# Controller.net
KiCad netlist of a schematic drawn in Altium Designer
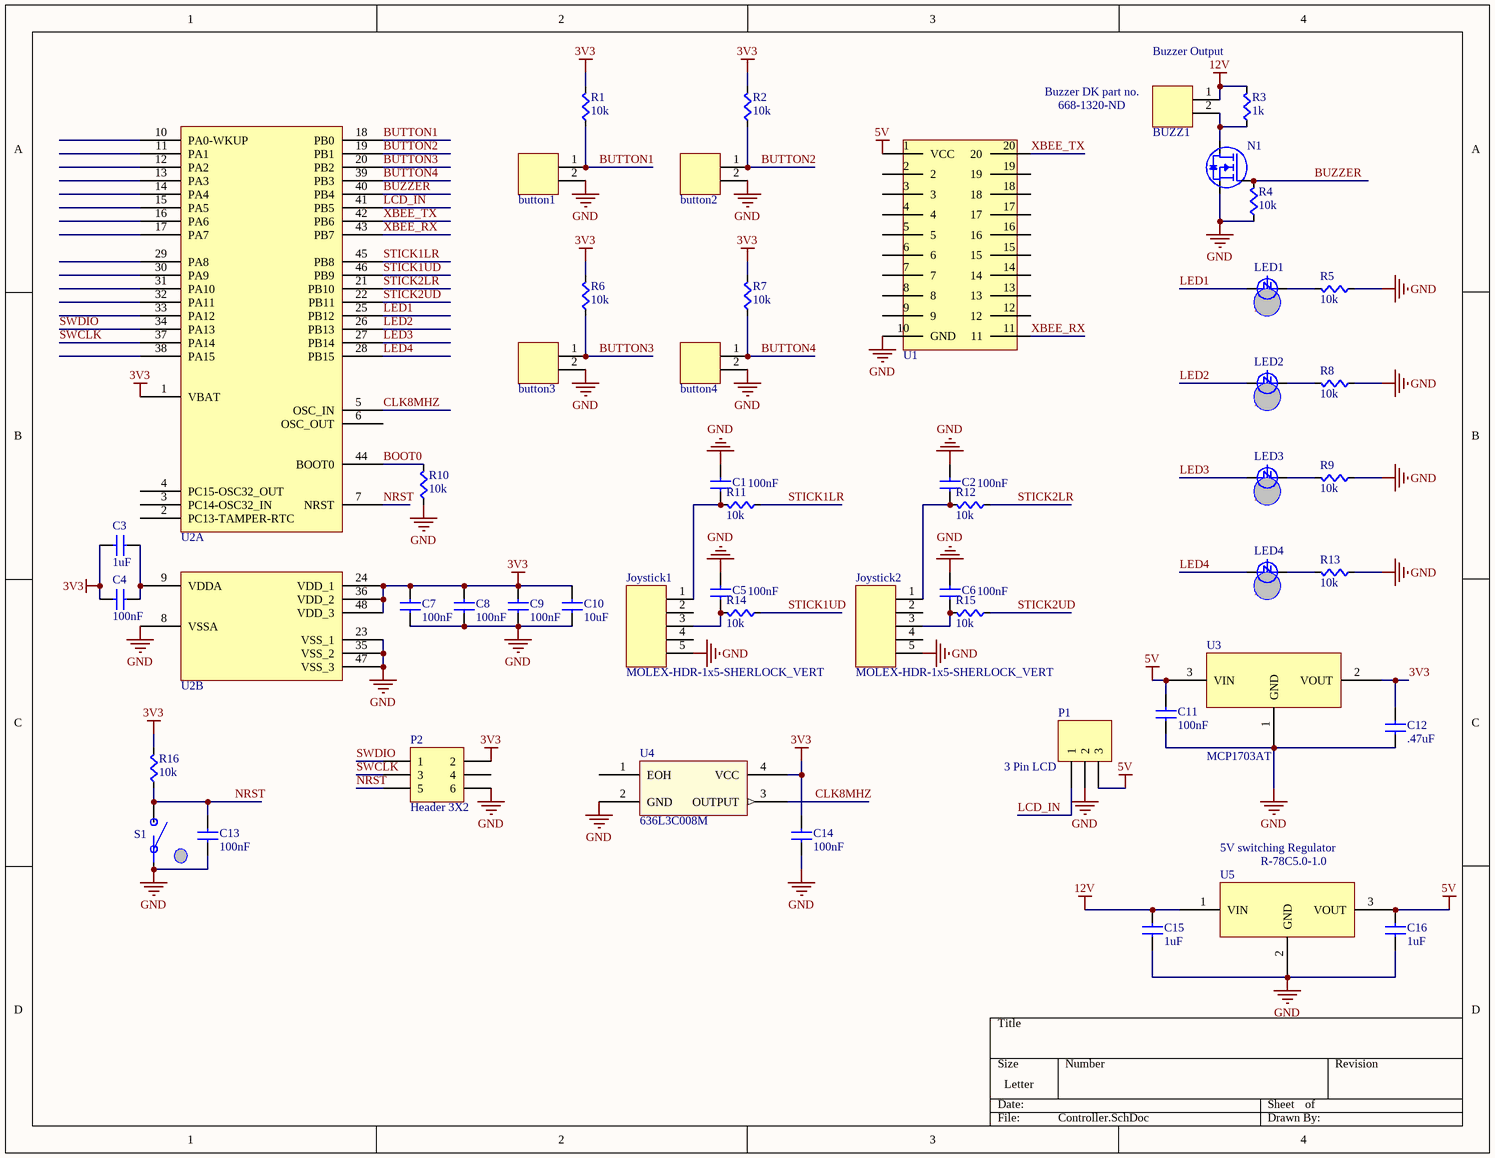
[diagram p0: Controller.SchDoc]

(export (version "E")
  (design (tool "Eeschema 10.0.6"))
  (components
    (comp (ref "button1")
      (value "2-pin Horz Sherlock")
      (footprint "MOLEX-HDR-1X2-SHERLOCK-HORZ")
      (fields
        (field (name "MANUFACTURER PART NUMBER") "0353630260")
        (field (name "MANUFACTURER") "Molex Inc")
      )
      (libsource (lib "SubjuGator8") (part "MOLEX-HDR-1x2-SHERLOCK_RA"))
    )
    (comp (ref "button2")
      (value "2-pin Horz Sherlock")
      (footprint "MOLEX-HDR-1X2-SHERLOCK-HORZ")
      (fields
        (field (name "MANUFACTURER PART NUMBER") "0353630260")
        (field (name "MANUFACTURER") "Molex Inc")
      )
      (libsource (lib "SubjuGator8") (part "MOLEX-HDR-1x2-SHERLOCK_RA"))
    )
    (comp (ref "button3")
      (value "2-pin Horz Sherlock")
      (footprint "MOLEX-HDR-1X2-SHERLOCK-HORZ")
      (fields
        (field (name "MANUFACTURER PART NUMBER") "0353630260")
        (field (name "MANUFACTURER") "Molex Inc")
      )
      (libsource (lib "SubjuGator8") (part "MOLEX-HDR-1x2-SHERLOCK_RA"))
    )
    (comp (ref "button4")
      (value "2-pin Horz Sherlock")
      (footprint "MOLEX-HDR-1X2-SHERLOCK-HORZ")
      (fields
        (field (name "MANUFACTURER PART NUMBER") "0353630260")
        (field (name "MANUFACTURER") "Molex Inc")
      )
      (libsource (lib "SubjuGator8") (part "MOLEX-HDR-1x2-SHERLOCK_RA"))
    )
    (comp (ref "BUZZ1")
      (value "2-pin Horz Sherlock")
      (footprint "MOLEX-HDR-1X2-SHERLOCK-HORZ")
      (fields
        (field (name "MANUFACTURER PART NUMBER") "0353630260")
        (field (name "MANUFACTURER") "Molex Inc")
      )
      (libsource (lib "SubjuGator8") (part "MOLEX-HDR-1x2-SHERLOCK_RA"))
    )
    (comp (ref "C1")
      (value "100nF")
      (footprint "CAPC0603")
      (fields (field (name "Comment") "Cap"))
      (libsource (lib "SubjuGator8") (part "Cap"))
    )
    (comp (ref "C2")
      (value "100nF")
      (footprint "CAPC0603")
      (fields (field (name "Comment") "Cap"))
      (libsource (lib "SubjuGator8") (part "Cap"))
    )
    (comp (ref "C3")
      (value "1uF")
      (footprint "CAPC0603")
      (fields (field (name "Comment") "Cap"))
      (libsource (lib "SubjuGator8") (part "Cap"))
    )
    (comp (ref "C4")
      (value "100nF")
      (footprint "CAPC0603")
      (fields (field (name "Comment") "Cap"))
      (libsource (lib "SubjuGator8") (part "Cap"))
    )
    (comp (ref "C5")
      (value "100nF")
      (footprint "CAPC0603")
      (fields (field (name "Comment") "Cap"))
      (libsource (lib "SubjuGator8") (part "Cap"))
    )
    (comp (ref "C6")
      (value "100nF")
      (footprint "CAPC0603")
      (fields (field (name "Comment") "Cap"))
      (libsource (lib "SubjuGator8") (part "Cap"))
    )
    (comp (ref "C7")
      (value "100nF")
      (footprint "CAPC0603")
      (fields (field (name "Comment") "Cap"))
      (libsource (lib "SubjuGator8") (part "Cap"))
    )
    (comp (ref "C8")
      (value "100nF")
      (footprint "CAPC0603")
      (fields (field (name "Comment") "Cap"))
      (libsource (lib "SubjuGator8") (part "Cap"))
    )
    (comp (ref "C9")
      (value "100nF")
      (footprint "CAPC0603")
      (fields (field (name "Comment") "Cap"))
      (libsource (lib "SubjuGator8") (part "Cap"))
    )
    (comp (ref "C10")
      (value "10uF")
      (footprint "CAPC1206")
      (fields (field (name "Comment") "Cap"))
      (libsource (lib "SubjuGator8") (part "Cap"))
    )
    (comp (ref "C11")
      (value "100nF")
      (footprint "CAPC1206")
      (fields (field (name "Comment") "Cap"))
      (libsource (lib "SubjuGator8") (part "Cap"))
    )
    (comp (ref "C12")
      (value ".47uF")
      (footprint "CAPC1206")
      (fields (field (name "Comment") "Cap"))
      (libsource (lib "SubjuGator8") (part "Cap"))
    )
    (comp (ref "C13")
      (value "100nF")
      (footprint "CAPC0603")
      (fields (field (name "Comment") "Cap"))
      (libsource (lib "SubjuGator8") (part "Cap"))
    )
    (comp (ref "C14")
      (value "100nF")
      (footprint "CAPC0603")
      (fields (field (name "Comment") "Cap"))
      (libsource (lib "SubjuGator8") (part "Cap"))
    )
    (comp (ref "C15")
      (value "1uF")
      (footprint "CAPC1206")
      (fields (field (name "Comment") "Cap"))
      (libsource (lib "SubjuGator8") (part "Cap"))
    )
    (comp (ref "C16")
      (value "1uF")
      (footprint "CAPC1206")
      (fields (field (name "Comment") "Cap"))
      (libsource (lib "SubjuGator8") (part "Cap"))
    )
    (comp (ref "Joystick1")
      (value "MOLEX-HDR-1x5-SHERLOCK_VERT")
      (footprint "MOLEX-HDR-1X5-SHERLOCK-VERT")
      (libsource (lib "SubjuGator8") (part "MOLEX-HDR-1x5-SHERLOCK_VERT"))
    )
    (comp (ref "Joystick2")
      (value "MOLEX-HDR-1x5-SHERLOCK_VERT")
      (footprint "MOLEX-HDR-1X5-SHERLOCK-VERT")
      (libsource (lib "SubjuGator8") (part "MOLEX-HDR-1x5-SHERLOCK_VERT"))
    )
    (comp (ref "LED1")
      (value "LED")
      (footprint "LED0603")
      (fields (field (name "COLOR") "Red"))
      (libsource (lib "SubjuGator8") (part "LED"))
    )
    (comp (ref "LED2")
      (value "LED")
      (footprint "LED0603")
      (fields (field (name "COLOR") "Red"))
      (libsource (lib "SubjuGator8") (part "LED"))
    )
    (comp (ref "LED3")
      (value "LED")
      (footprint "LED0603")
      (fields (field (name "COLOR") "Red"))
      (libsource (lib "SubjuGator8") (part "LED"))
    )
    (comp (ref "LED4")
      (value "LED")
      (footprint "LED0603")
      (fields (field (name "COLOR") "Red"))
      (libsource (lib "SubjuGator8") (part "LED"))
    )
    (comp (ref "N1")
      (value "NMOSFET")
      (footprint "2N7002P,215")
      (description "NMOSFET Template")
      (libsource (lib "SubjuGator8") (part "NMOSFET"))
    )
    (comp (ref "P1")
      (value "3 Pin LCD")
      (footprint "HDR1X3")
      (description "NHD-0420D3Z-NSW-BBW-V3-ND")
      (fields (field (name "PUBLISHER") "Altium Limited"))
      (libsource (lib "Miscellaneous Connectors") (part "Header 3"))
    )
    (comp (ref "P2")
      (value "Header 3X2")
      (footprint "HDR2X3")
      (description "Header, 3-Pin, Dual row")
      (fields (field (name "PUBLISHER") "Altium Limited"))
      (libsource (lib "Miscellaneous Connectors") (part "Header 3X2"))
    )
    (comp (ref "R1")
      (value "10k")
      (footprint "RES0603")
      (fields (field (name "Comment") "Res"))
      (libsource (lib "SubjuGator8") (part "Res"))
    )
    (comp (ref "R2")
      (value "10k")
      (footprint "RES0603")
      (fields (field (name "Comment") "Res"))
      (libsource (lib "SubjuGator8") (part "Res"))
    )
    (comp (ref "R3")
      (value "1k")
      (footprint "RES0603")
      (fields (field (name "Comment") "Res"))
      (libsource (lib "SubjuGator8") (part "Res"))
    )
    (comp (ref "R4")
      (value "10k")
      (footprint "RES0603")
      (fields (field (name "Comment") "Res"))
      (libsource (lib "SubjuGator8") (part "Res"))
    )
    (comp (ref "R5")
      (value "10k")
      (footprint "RES0603")
      (fields (field (name "Comment") "Res"))
      (libsource (lib "SubjuGator8") (part "Res"))
    )
    (comp (ref "R6")
      (value "10k")
      (footprint "RES0603")
      (fields (field (name "Comment") "Res"))
      (libsource (lib "SubjuGator8") (part "Res"))
    )
    (comp (ref "R7")
      (value "10k")
      (footprint "RES0603")
      (fields (field (name "Comment") "Res"))
      (libsource (lib "SubjuGator8") (part "Res"))
    )
    (comp (ref "R8")
      (value "10k")
      (footprint "RES0603")
      (fields (field (name "Comment") "Res"))
      (libsource (lib "SubjuGator8") (part "Res"))
    )
    (comp (ref "R9")
      (value "10k")
      (footprint "RES0603")
      (fields (field (name "Comment") "Res"))
      (libsource (lib "SubjuGator8") (part "Res"))
    )
    (comp (ref "R10")
      (value "10k")
      (footprint "RES0603")
      (fields (field (name "Comment") "Res"))
      (libsource (lib "SubjuGator8") (part "Res"))
    )
    (comp (ref "R11")
      (value "10k")
      (footprint "RES0603")
      (fields (field (name "Comment") "Res"))
      (libsource (lib "SubjuGator8") (part "Res"))
    )
    (comp (ref "R12")
      (value "10k")
      (footprint "RES0603")
      (fields (field (name "Comment") "Res"))
      (libsource (lib "SubjuGator8") (part "Res"))
    )
    (comp (ref "R13")
      (value "10k")
      (footprint "RES0603")
      (fields (field (name "Comment") "Res"))
      (libsource (lib "SubjuGator8") (part "Res"))
    )
    (comp (ref "R14")
      (value "10k")
      (footprint "RES0603")
      (fields (field (name "Comment") "Res"))
      (libsource (lib "SubjuGator8") (part "Res"))
    )
    (comp (ref "R15")
      (value "10k")
      (footprint "RES0603")
      (fields (field (name "Comment") "Res"))
      (libsource (lib "SubjuGator8") (part "Res"))
    )
    (comp (ref "R16")
      (value "10k")
      (footprint "RES0603")
      (fields (field (name "Comment") "Res"))
      (libsource (lib "SubjuGator8") (part "Res"))
    )
    (comp (ref "S1")
      (value "Button")
      (footprint "PTS645xxxxSMTR92")
      (description "SPST Button")
      (libsource (lib "SubjuGator8") (part "Button"))
    )
    (comp (ref "U1")
      (value "XBee")
      (footprint "XBee")
      (description "XBee radio")
      (libsource (lib "SubjuGator8") (part "XBee"))
    )
    (comp (ref "U2")
      (value "STM32F103C8T7")
      (footprint "STM32F103C8T7")
      (description "MCU ARM 32BIT 64K FLASH 48-LQFP")
      (libsource (lib "SubjuGator8") (part "STM32F103C8T7"))
    )
    (comp (ref "U3")
      (value "MCP1703AT")
      (footprint "MCP1703AT-xx02EDB")
      (description "250 mA, 16V, Low Quiescent Current LDO Regulator")
      (libsource (lib "SubjuGator8") (part "MCP1703AT"))
    )
    (comp (ref "U4")
      (value "636L3C008M")
      (footprint "636L3C")
      (description "HCMOS/TTL Clock Oscillator")
      (libsource (lib "SubjuGator8") (part "636L3C"))
    )
    (comp (ref "U5")
      (value "R-78C5.0-1.0")
      (footprint "R-78C5.0-1.0")
      (description "CONV DC/DC 1A 5V OUT SIP VERT")
      (libsource (lib "SubjuGator8") (part "R-78C5.0-1.0"))
    )
  )
  (nets
    (net (code "1") (name "/BOOT0") (class "Default")
      (node (ref "R10") (pin "1") (pinfunction "A_1") (pintype "passive"))
      (node (ref "U2") (pin "44") (pinfunction "BOOT0_44") (pintype "passive"))
    )
    (net (code "2") (name "/BUTTON1") (class "Default")
      (node (ref "R1") (pin "2") (pinfunction "B_2") (pintype "passive"))
      (node (ref "U2") (pin "18") (pinfunction "PB0_18") (pintype "passive"))
      (node (ref "button1") (pin "1") (pinfunction "1_1") (pintype "passive"))
    )
    (net (code "3") (name "/BUTTON2") (class "Default")
      (node (ref "R2") (pin "2") (pinfunction "B_2") (pintype "passive"))
      (node (ref "U2") (pin "19") (pinfunction "PB1_19") (pintype "passive"))
      (node (ref "button2") (pin "1") (pinfunction "1_1") (pintype "passive"))
    )
    (net (code "4") (name "/BUTTON3") (class "Default")
      (node (ref "R6") (pin "2") (pinfunction "B_2") (pintype "passive"))
      (node (ref "U2") (pin "20") (pinfunction "PB2_20") (pintype "passive"))
      (node (ref "button3") (pin "1") (pinfunction "1_1") (pintype "passive"))
    )
    (net (code "5") (name "/BUTTON4") (class "Default")
      (node (ref "R7") (pin "2") (pinfunction "B_2") (pintype "passive"))
      (node (ref "U2") (pin "39") (pinfunction "PB3_39") (pintype "passive"))
      (node (ref "button4") (pin "1") (pinfunction "1_1") (pintype "passive"))
    )
    (net (code "6") (name "/BUZZER") (class "Default")
      (node (ref "N1") (pin "1") (pinfunction "G_1") (pintype "passive"))
      (node (ref "R4") (pin "1") (pinfunction "A_1") (pintype "passive"))
      (node (ref "U2") (pin "40") (pinfunction "PB4_40") (pintype "passive"))
    )
    (net (code "7") (name "/CLK8MHZ") (class "Default")
      (node (ref "U2") (pin "5") (pinfunction "OSC_IN_5") (pintype "passive"))
      (node (ref "U4") (pin "3") (pinfunction "OUTPUT_3") (pintype "output"))
    )
    (net (code "8") (name "/LCD_IN") (class "Default")
      (node (ref "P1") (pin "1") (pinfunction "1_1") (pintype "passive"))
      (node (ref "U2") (pin "41") (pinfunction "PB5_41") (pintype "passive"))
    )
    (net (code "9") (name "/LED1") (class "Default")
      (node (ref "LED1") (pin "A") (pinfunction "A_A") (pintype "passive"))
      (node (ref "U2") (pin "25") (pinfunction "PB12_25") (pintype "passive"))
    )
    (net (code "10") (name "/LED2") (class "Default")
      (node (ref "LED2") (pin "A") (pinfunction "A_A") (pintype "passive"))
      (node (ref "U2") (pin "26") (pinfunction "PB13_26") (pintype "passive"))
    )
    (net (code "11") (name "/LED3") (class "Default")
      (node (ref "LED3") (pin "A") (pinfunction "A_A") (pintype "passive"))
      (node (ref "U2") (pin "27") (pinfunction "PB14_27") (pintype "passive"))
    )
    (net (code "12") (name "/LED4") (class "Default")
      (node (ref "LED4") (pin "A") (pinfunction "A_A") (pintype "passive"))
      (node (ref "U2") (pin "28") (pinfunction "PB15_28") (pintype "passive"))
    )
    (net (code "13") (name "/NRST") (class "Default")
      (node (ref "C13") (pin "1") (pinfunction "A_1") (pintype "passive"))
      (node (ref "P2") (pin "5") (pinfunction "5_5") (pintype "passive"))
      (node (ref "R16") (pin "2") (pinfunction "B_2") (pintype "passive"))
      (node (ref "S1") (pin "B") (pinfunction "B_B") (pintype "passive"))
      (node (ref "U2") (pin "7") (pinfunction "NRST_7") (pintype "passive"))
    )
    (net (code "14") (name "/STICK1LR") (class "Default")
      (node (ref "R11") (pin "2") (pinfunction "B_2") (pintype "passive"))
      (node (ref "U2") (pin "45") (pinfunction "PB8_45") (pintype "passive"))
    )
    (net (code "15") (name "/STICK1UD") (class "Default")
      (node (ref "R14") (pin "2") (pinfunction "B_2") (pintype "passive"))
      (node (ref "U2") (pin "46") (pinfunction "PB9_46") (pintype "passive"))
    )
    (net (code "16") (name "/STICK2LR") (class "Default")
      (node (ref "R12") (pin "2") (pinfunction "B_2") (pintype "passive"))
      (node (ref "U2") (pin "21") (pinfunction "PB10_21") (pintype "passive"))
    )
    (net (code "17") (name "/STICK2UD") (class "Default")
      (node (ref "R15") (pin "2") (pinfunction "B_2") (pintype "passive"))
      (node (ref "U2") (pin "22") (pinfunction "PB11_22") (pintype "passive"))
    )
    (net (code "18") (name "/SWCLK") (class "Default")
      (node (ref "P2") (pin "3") (pinfunction "3_3") (pintype "passive"))
      (node (ref "U2") (pin "37") (pinfunction "PA14_37") (pintype "passive"))
    )
    (net (code "19") (name "/SWDIO") (class "Default")
      (node (ref "P2") (pin "1") (pinfunction "1_1") (pintype "passive"))
      (node (ref "U2") (pin "34") (pinfunction "PA13_34") (pintype "passive"))
    )
    (net (code "20") (name "/XBEE_RX") (class "Default")
      (node (ref "U1") (pin "11") (pinfunction "11_11") (pintype "passive"))
      (node (ref "U2") (pin "43") (pinfunction "PB7_43") (pintype "passive"))
    )
    (net (code "21") (name "/XBEE_TX") (class "Default")
      (node (ref "U1") (pin "20") (pinfunction "20_20") (pintype "passive"))
      (node (ref "U2") (pin "42") (pinfunction "PB6_42") (pintype "passive"))
    )
    (net (code "22") (name "3V3") (class "Default")
      (node (ref "C10") (pin "2") (pinfunction "B_2") (pintype "passive"))
      (node (ref "C12") (pin "1") (pinfunction "A_1") (pintype "passive"))
      (node (ref "C14") (pin "1") (pinfunction "A_1") (pintype "passive"))
      (node (ref "C3") (pin "2") (pinfunction "B_2") (pintype "passive"))
      (node (ref "C4") (pin "2") (pinfunction "B_2") (pintype "passive"))
      (node (ref "C7") (pin "1") (pinfunction "A_1") (pintype "passive"))
      (node (ref "C8") (pin "1") (pinfunction "A_1") (pintype "passive"))
      (node (ref "C9") (pin "1") (pinfunction "A_1") (pintype "passive"))
      (node (ref "P2") (pin "2") (pinfunction "2_2") (pintype "passive"))
      (node (ref "R1") (pin "1") (pinfunction "A_1") (pintype "passive"))
      (node (ref "R16") (pin "1") (pinfunction "A_1") (pintype "passive"))
      (node (ref "R2") (pin "1") (pinfunction "A_1") (pintype "passive"))
      (node (ref "R6") (pin "1") (pinfunction "A_1") (pintype "passive"))
      (node (ref "R7") (pin "1") (pinfunction "A_1") (pintype "passive"))
      (node (ref "U2") (pin "1") (pinfunction "VBAT_1") (pintype "passive"))
      (node (ref "U2") (pin "24") (pinfunction "VDD_1_24") (pintype "passive"))
      (node (ref "U2") (pin "36") (pinfunction "VDD_2_36") (pintype "passive"))
      (node (ref "U2") (pin "48") (pinfunction "VDD_3_48") (pintype "passive"))
      (node (ref "U3") (pin "2") (pinfunction "VOUT_2") (pintype "passive"))
      (node (ref "U4") (pin "4") (pinfunction "VCC_4") (pintype "power_in"))
    )
    (net (code "23") (name "5V") (class "Default")
      (node (ref "C11") (pin "1") (pinfunction "A_1") (pintype "passive"))
      (node (ref "C16") (pin "1") (pinfunction "A_1") (pintype "passive"))
      (node (ref "P1") (pin "3") (pinfunction "3_3") (pintype "passive"))
      (node (ref "U1") (pin "1") (pinfunction "VCC_1") (pintype "passive"))
      (node (ref "U3") (pin "3") (pinfunction "VIN_3") (pintype "passive"))
      (node (ref "U5") (pin "3") (pinfunction "VOUT_3") (pintype "passive"))
    )
    (net (code "24") (name "12V") (class "Default")
      (node (ref "BUZZ1") (pin "1") (pinfunction "1_1") (pintype "passive"))
      (node (ref "C15") (pin "1") (pinfunction "A_1") (pintype "passive"))
      (node (ref "R3") (pin "1") (pinfunction "A_1") (pintype "passive"))
      (node (ref "U5") (pin "1") (pinfunction "VIN_1") (pintype "passive"))
    )
    (net (code "25") (name "GND") (class "Default")
      (node (ref "C1") (pin "1") (pinfunction "A_1") (pintype "passive"))
      (node (ref "C10") (pin "1") (pinfunction "A_1") (pintype "passive"))
      (node (ref "C11") (pin "2") (pinfunction "B_2") (pintype "passive"))
      (node (ref "C12") (pin "2") (pinfunction "B_2") (pintype "passive"))
      (node (ref "C13") (pin "2") (pinfunction "B_2") (pintype "passive"))
      (node (ref "C14") (pin "2") (pinfunction "B_2") (pintype "passive"))
      (node (ref "C15") (pin "2") (pinfunction "B_2") (pintype "passive"))
      (node (ref "C16") (pin "2") (pinfunction "B_2") (pintype "passive"))
      (node (ref "C2") (pin "1") (pinfunction "A_1") (pintype "passive"))
      (node (ref "C5") (pin "1") (pinfunction "A_1") (pintype "passive"))
      (node (ref "C6") (pin "1") (pinfunction "A_1") (pintype "passive"))
      (node (ref "C7") (pin "2") (pinfunction "B_2") (pintype "passive"))
      (node (ref "C8") (pin "2") (pinfunction "B_2") (pintype "passive"))
      (node (ref "C9") (pin "2") (pinfunction "B_2") (pintype "passive"))
      (node (ref "Joystick1") (pin "5") (pinfunction "5_5") (pintype "passive"))
      (node (ref "Joystick2") (pin "5") (pinfunction "5_5") (pintype "passive"))
      (node (ref "N1") (pin "2") (pinfunction "S_2") (pintype "passive"))
      (node (ref "P1") (pin "2") (pinfunction "2_2") (pintype "passive"))
      (node (ref "P2") (pin "6") (pinfunction "6_6") (pintype "passive"))
      (node (ref "R10") (pin "2") (pinfunction "B_2") (pintype "passive"))
      (node (ref "R13") (pin "2") (pinfunction "B_2") (pintype "passive"))
      (node (ref "R4") (pin "2") (pinfunction "B_2") (pintype "passive"))
      (node (ref "R5") (pin "2") (pinfunction "B_2") (pintype "passive"))
      (node (ref "R8") (pin "2") (pinfunction "B_2") (pintype "passive"))
      (node (ref "R9") (pin "2") (pinfunction "B_2") (pintype "passive"))
      (node (ref "S1") (pin "A") (pinfunction "A_A") (pintype "passive"))
      (node (ref "U1") (pin "10") (pinfunction "GND_10") (pintype "passive"))
      (node (ref "U2") (pin "23") (pinfunction "VSS_1_23") (pintype "passive"))
      (node (ref "U2") (pin "35") (pinfunction "VSS_2_35") (pintype "passive"))
      (node (ref "U2") (pin "47") (pinfunction "VSS_3_47") (pintype "passive"))
      (node (ref "U2") (pin "8") (pinfunction "VSSA_8") (pintype "passive"))
      (node (ref "U3") (pin "1") (pinfunction "GND_1") (pintype "power_in"))
      (node (ref "U4") (pin "2") (pinfunction "GND_2") (pintype "power_in"))
      (node (ref "U5") (pin "2") (pinfunction "GND_2") (pintype "power_in"))
      (node (ref "button1") (pin "2") (pinfunction "2_2") (pintype "passive"))
      (node (ref "button2") (pin "2") (pinfunction "2_2") (pintype "passive"))
      (node (ref "button3") (pin "2") (pinfunction "2_2") (pintype "passive"))
      (node (ref "button4") (pin "2") (pinfunction "2_2") (pintype "passive"))
    )
    (net (code "26") (name "Net-(C1-B)") (class "Default")
      (node (ref "C1") (pin "2") (pinfunction "B_2") (pintype "passive"))
      (node (ref "Joystick1") (pin "1") (pinfunction "1_1") (pintype "passive"))
      (node (ref "R11") (pin "1") (pinfunction "A_1") (pintype "passive"))
    )
    (net (code "27") (name "Net-(C2-B)") (class "Default")
      (node (ref "C2") (pin "2") (pinfunction "B_2") (pintype "passive"))
      (node (ref "Joystick2") (pin "1") (pinfunction "1_1") (pintype "passive"))
      (node (ref "R12") (pin "1") (pinfunction "A_1") (pintype "passive"))
    )
    (net (code "28") (name "Net-(C3-A)") (class "Default")
      (node (ref "C3") (pin "1") (pinfunction "A_1") (pintype "passive"))
      (node (ref "C4") (pin "1") (pinfunction "A_1") (pintype "passive"))
      (node (ref "U2") (pin "9") (pinfunction "VDDA_9") (pintype "passive"))
    )
    (net (code "29") (name "Net-(C5-B)") (class "Default")
      (node (ref "C5") (pin "2") (pinfunction "B_2") (pintype "passive"))
      (node (ref "Joystick1") (pin "3") (pinfunction "3_3") (pintype "passive"))
      (node (ref "R14") (pin "1") (pinfunction "A_1") (pintype "passive"))
    )
    (net (code "30") (name "Net-(C6-B)") (class "Default")
      (node (ref "C6") (pin "2") (pinfunction "B_2") (pintype "passive"))
      (node (ref "Joystick2") (pin "3") (pinfunction "3_3") (pintype "passive"))
      (node (ref "R15") (pin "1") (pinfunction "A_1") (pintype "passive"))
    )
    (net (code "31") (name "Net-(N1-D)") (class "Default")
      (node (ref "BUZZ1") (pin "2") (pinfunction "2_2") (pintype "passive"))
      (node (ref "N1") (pin "3") (pinfunction "D_3") (pintype "passive"))
      (node (ref "R3") (pin "2") (pinfunction "B_2") (pintype "passive"))
    )
    (net (code "32") (name "Net-(R5-A)") (class "Default")
      (node (ref "LED1") (pin "C") (pinfunction "C_C") (pintype "passive"))
      (node (ref "R5") (pin "1") (pinfunction "A_1") (pintype "passive"))
    )
    (net (code "33") (name "Net-(R8-A)") (class "Default")
      (node (ref "LED2") (pin "C") (pinfunction "C_C") (pintype "passive"))
      (node (ref "R8") (pin "1") (pinfunction "A_1") (pintype "passive"))
    )
    (net (code "34") (name "Net-(R9-A)") (class "Default")
      (node (ref "LED3") (pin "C") (pinfunction "C_C") (pintype "passive"))
      (node (ref "R9") (pin "1") (pinfunction "A_1") (pintype "passive"))
    )
    (net (code "35") (name "Net-(R13-A)") (class "Default")
      (node (ref "LED4") (pin "C") (pinfunction "C_C") (pintype "passive"))
      (node (ref "R13") (pin "1") (pinfunction "A_1") (pintype "passive"))
    )
    (net (code "36") (name "unconnected-(Joystick1-Pad2)") (class "Default")
      (node (ref "Joystick1") (pin "2") (pinfunction "2_2") (pintype "passive"))
    )
    (net (code "37") (name "unconnected-(Joystick1-Pad4)") (class "Default")
      (node (ref "Joystick1") (pin "4") (pinfunction "4_4") (pintype "passive"))
    )
    (net (code "38") (name "unconnected-(Joystick2-Pad2)") (class "Default")
      (node (ref "Joystick2") (pin "2") (pinfunction "2_2") (pintype "passive"))
    )
    (net (code "39") (name "unconnected-(Joystick2-Pad4)") (class "Default")
      (node (ref "Joystick2") (pin "4") (pinfunction "4_4") (pintype "passive"))
    )
    (net (code "40") (name "unconnected-(P2-Pad4)") (class "Default")
      (node (ref "P2") (pin "4") (pinfunction "4_4") (pintype "passive"))
    )
    (net (code "41") (name "unconnected-(U1-Pad2)") (class "Default")
      (node (ref "U1") (pin "2") (pinfunction "2_2") (pintype "passive"))
    )
    (net (code "42") (name "unconnected-(U1-Pad3)") (class "Default")
      (node (ref "U1") (pin "3") (pinfunction "3_3") (pintype "passive"))
    )
    (net (code "43") (name "unconnected-(U1-Pad4)") (class "Default")
      (node (ref "U1") (pin "4") (pinfunction "4_4") (pintype "passive"))
    )
    (net (code "44") (name "unconnected-(U1-Pad5)") (class "Default")
      (node (ref "U1") (pin "5") (pinfunction "5_5") (pintype "passive"))
    )
    (net (code "45") (name "unconnected-(U1-Pad6)") (class "Default")
      (node (ref "U1") (pin "6") (pinfunction "6_6") (pintype "passive"))
    )
    (net (code "46") (name "unconnected-(U1-Pad7)") (class "Default")
      (node (ref "U1") (pin "7") (pinfunction "7_7") (pintype "passive"))
    )
    (net (code "47") (name "unconnected-(U1-Pad8)") (class "Default")
      (node (ref "U1") (pin "8") (pinfunction "8_8") (pintype "passive"))
    )
    (net (code "48") (name "unconnected-(U1-Pad9)") (class "Default")
      (node (ref "U1") (pin "9") (pinfunction "9_9") (pintype "passive"))
    )
    (net (code "49") (name "unconnected-(U1-Pad12)") (class "Default")
      (node (ref "U1") (pin "12") (pinfunction "12_12") (pintype "passive"))
    )
    (net (code "50") (name "unconnected-(U1-Pad13)") (class "Default")
      (node (ref "U1") (pin "13") (pinfunction "13_13") (pintype "passive"))
    )
    (net (code "51") (name "unconnected-(U1-Pad14)") (class "Default")
      (node (ref "U1") (pin "14") (pinfunction "14_14") (pintype "passive"))
    )
    (net (code "52") (name "unconnected-(U1-Pad15)") (class "Default")
      (node (ref "U1") (pin "15") (pinfunction "15_15") (pintype "passive"))
    )
    (net (code "53") (name "unconnected-(U1-Pad16)") (class "Default")
      (node (ref "U1") (pin "16") (pinfunction "16_16") (pintype "passive"))
    )
    (net (code "54") (name "unconnected-(U1-Pad17)") (class "Default")
      (node (ref "U1") (pin "17") (pinfunction "17_17") (pintype "passive"))
    )
    (net (code "55") (name "unconnected-(U1-Pad18)") (class "Default")
      (node (ref "U1") (pin "18") (pinfunction "18_18") (pintype "passive"))
    )
    (net (code "56") (name "unconnected-(U1-Pad19)") (class "Default")
      (node (ref "U1") (pin "19") (pinfunction "19_19") (pintype "passive"))
    )
    (net (code "57") (name "unconnected-(U2A-OSC_OUT-Pad6)") (class "Default")
      (node (ref "U2") (pin "6") (pinfunction "OSC_OUT_6") (pintype "passive"))
    )
    (net (code "58") (name "unconnected-(U2A-PA0-WKUP-Pad10)") (class "Default")
      (node (ref "U2") (pin "10") (pinfunction "PA0-WKUP_10") (pintype "passive"))
    )
    (net (code "59") (name "unconnected-(U2A-PA1-Pad11)") (class "Default")
      (node (ref "U2") (pin "11") (pinfunction "PA1_11") (pintype "passive"))
    )
    (net (code "60") (name "unconnected-(U2A-PA2-Pad12)") (class "Default")
      (node (ref "U2") (pin "12") (pinfunction "PA2_12") (pintype "passive"))
    )
    (net (code "61") (name "unconnected-(U2A-PA3-Pad13)") (class "Default")
      (node (ref "U2") (pin "13") (pinfunction "PA3_13") (pintype "passive"))
    )
    (net (code "62") (name "unconnected-(U2A-PA4-Pad14)") (class "Default")
      (node (ref "U2") (pin "14") (pinfunction "PA4_14") (pintype "passive"))
    )
    (net (code "63") (name "unconnected-(U2A-PA5-Pad15)") (class "Default")
      (node (ref "U2") (pin "15") (pinfunction "PA5_15") (pintype "passive"))
    )
    (net (code "64") (name "unconnected-(U2A-PA6-Pad16)") (class "Default")
      (node (ref "U2") (pin "16") (pinfunction "PA6_16") (pintype "passive"))
    )
    (net (code "65") (name "unconnected-(U2A-PA7-Pad17)") (class "Default")
      (node (ref "U2") (pin "17") (pinfunction "PA7_17") (pintype "passive"))
    )
    (net (code "66") (name "unconnected-(U2A-PA8-Pad29)") (class "Default")
      (node (ref "U2") (pin "29") (pinfunction "PA8_29") (pintype "passive"))
    )
    (net (code "67") (name "unconnected-(U2A-PA9-Pad30)") (class "Default")
      (node (ref "U2") (pin "30") (pinfunction "PA9_30") (pintype "passive"))
    )
    (net (code "68") (name "unconnected-(U2A-PA10-Pad31)") (class "Default")
      (node (ref "U2") (pin "31") (pinfunction "PA10_31") (pintype "passive"))
    )
    (net (code "69") (name "unconnected-(U2A-PA11-Pad32)") (class "Default")
      (node (ref "U2") (pin "32") (pinfunction "PA11_32") (pintype "passive"))
    )
    (net (code "70") (name "unconnected-(U2A-PA12-Pad33)") (class "Default")
      (node (ref "U2") (pin "33") (pinfunction "PA12_33") (pintype "passive"))
    )
    (net (code "71") (name "unconnected-(U2A-PA15-Pad38)") (class "Default")
      (node (ref "U2") (pin "38") (pinfunction "PA15_38") (pintype "passive"))
    )
    (net (code "72") (name "unconnected-(U2A-PC13-TAMPER-RTC-Pad2)") (class "Default")
      (node (ref "U2") (pin "2") (pinfunction "PC13-TAMPER-RTC_2") (pintype "passive"))
    )
    (net (code "73") (name "unconnected-(U2A-PC14-OSC32_IN-Pad3)") (class "Default")
      (node (ref "U2") (pin "3") (pinfunction "PC14-OSC32_IN_3") (pintype "passive"))
    )
    (net (code "74") (name "unconnected-(U2A-PC15-OSC32_OUT-Pad4)") (class "Default")
      (node (ref "U2") (pin "4") (pinfunction "PC15-OSC32_OUT_4") (pintype "passive"))
    )
    (net (code "75") (name "unconnected-(U4-EOH-Pad1)") (class "Default")
      (node (ref "U4") (pin "1") (pinfunction "EOH_1") (pintype "passive"))
    )
  )
)
